# 9_7-13_3.net
KiCad netlist of a schematic drawn in Altium Designer
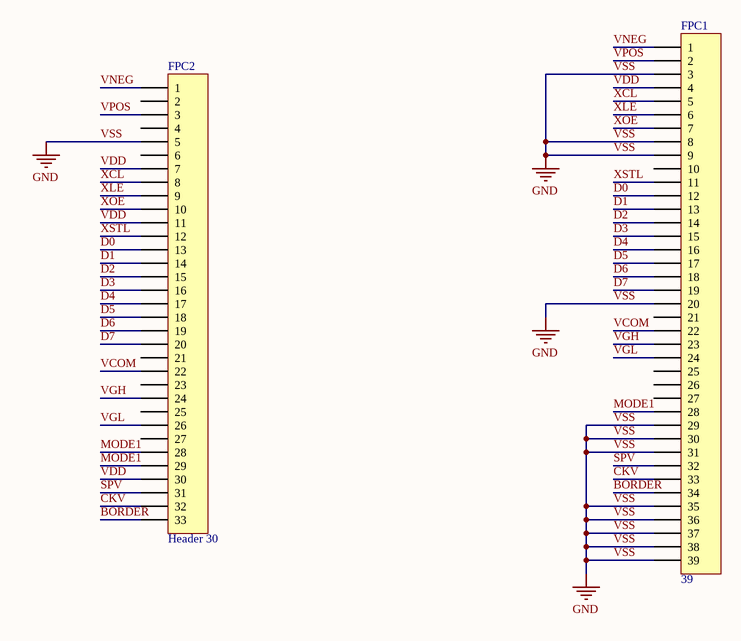
[diagram p0: 9.7-13.3.SchDoc]

(export (version "E")
  (design (tool "Eeschema 10.0.6"))
  (components
    (comp (ref "FPC1") (value "39") (footprint "1") (libsource (lib "9.7-13.3") (part "39")))
    (comp (ref "FPC2")
      (value "Header 30")
      (footprint "2")
      (description "Header, 30-Pin")
      (fields (field (name "PUBLISHER") "Altium Limited"))
      (libsource (lib "9.7-13.3") (part "Header 33"))
    )
  )
  (nets
    (net (code "2") (name "/BORDER") (class "Default")
      (node (ref "FPC1") (pin "34") (pinfunction "34_34") (pintype "passive"))
      (node (ref "FPC2") (pin "33") (pinfunction "33_33") (pintype "passive"))
    )
    (net (code "3") (name "/CKV") (class "Default")
      (node (ref "FPC1") (pin "33") (pinfunction "33_33") (pintype "passive"))
      (node (ref "FPC2") (pin "32") (pinfunction "32_32") (pintype "passive"))
    )
    (net (code "4") (name "/D0") (class "Default")
      (node (ref "FPC1") (pin "12") (pinfunction "12_12") (pintype "passive"))
      (node (ref "FPC2") (pin "13") (pinfunction "13_13") (pintype "passive"))
    )
    (net (code "5") (name "/D1") (class "Default")
      (node (ref "FPC1") (pin "13") (pinfunction "13_13") (pintype "passive"))
      (node (ref "FPC2") (pin "14") (pinfunction "14_14") (pintype "passive"))
    )
    (net (code "6") (name "/D2") (class "Default")
      (node (ref "FPC1") (pin "14") (pinfunction "14_14") (pintype "passive"))
      (node (ref "FPC2") (pin "15") (pinfunction "15_15") (pintype "passive"))
    )
    (net (code "7") (name "/D3") (class "Default")
      (node (ref "FPC1") (pin "15") (pinfunction "15_15") (pintype "passive"))
      (node (ref "FPC2") (pin "16") (pinfunction "16_16") (pintype "passive"))
    )
    (net (code "8") (name "/D4") (class "Default")
      (node (ref "FPC1") (pin "16") (pinfunction "16_16") (pintype "passive"))
      (node (ref "FPC2") (pin "17") (pinfunction "17_17") (pintype "passive"))
    )
    (net (code "9") (name "/D5") (class "Default")
      (node (ref "FPC1") (pin "17") (pinfunction "17_17") (pintype "passive"))
      (node (ref "FPC2") (pin "18") (pinfunction "18_18") (pintype "passive"))
    )
    (net (code "10") (name "/D6") (class "Default")
      (node (ref "FPC1") (pin "18") (pinfunction "18_18") (pintype "passive"))
      (node (ref "FPC2") (pin "19") (pinfunction "19_19") (pintype "passive"))
    )
    (net (code "11") (name "/D7") (class "Default")
      (node (ref "FPC1") (pin "19") (pinfunction "19_19") (pintype "passive"))
      (node (ref "FPC2") (pin "20") (pinfunction "20_20") (pintype "passive"))
    )
    (net (code "12") (name "/MODE1") (class "Default")
      (node (ref "FPC1") (pin "28") (pinfunction "28_28") (pintype "passive"))
      (node (ref "FPC2") (pin "28") (pinfunction "28_28") (pintype "passive"))
      (node (ref "FPC2") (pin "29") (pinfunction "29_29") (pintype "passive"))
    )
    (net (code "13") (name "/SPV") (class "Default")
      (node (ref "FPC1") (pin "32") (pinfunction "32_32") (pintype "passive"))
      (node (ref "FPC2") (pin "31") (pinfunction "31_31") (pintype "passive"))
    )
    (net (code "14") (name "/VCOM") (class "Default")
      (node (ref "FPC1") (pin "22") (pinfunction "22_22") (pintype "passive"))
      (node (ref "FPC2") (pin "22") (pinfunction "22_22") (pintype "passive"))
    )
    (net (code "15") (name "/VDD") (class "Default")
      (node (ref "FPC1") (pin "4") (pinfunction "4_4") (pintype "passive"))
      (node (ref "FPC2") (pin "11") (pinfunction "11_11") (pintype "passive"))
      (node (ref "FPC2") (pin "30") (pinfunction "30_30") (pintype "passive"))
      (node (ref "FPC2") (pin "7") (pinfunction "7_7") (pintype "passive"))
    )
    (net (code "16") (name "/VGH") (class "Default")
      (node (ref "FPC1") (pin "23") (pinfunction "23_23") (pintype "passive"))
      (node (ref "FPC2") (pin "24") (pinfunction "24_24") (pintype "passive"))
    )
    (net (code "17") (name "/VGL") (class "Default")
      (node (ref "FPC1") (pin "24") (pinfunction "24_24") (pintype "passive"))
      (node (ref "FPC2") (pin "26") (pinfunction "26_26") (pintype "passive"))
    )
    (net (code "18") (name "/VNEG") (class "Default")
      (node (ref "FPC1") (pin "1") (pinfunction "1_1") (pintype "passive"))
      (node (ref "FPC2") (pin "1") (pinfunction "1_1") (pintype "passive"))
    )
    (net (code "19") (name "/VPOS") (class "Default")
      (node (ref "FPC1") (pin "2") (pinfunction "2_2") (pintype "passive"))
      (node (ref "FPC2") (pin "3") (pinfunction "3_3") (pintype "passive"))
    )
    (net (code "20") (name "/XCL") (class "Default")
      (node (ref "FPC1") (pin "5") (pinfunction "5_5") (pintype "passive"))
      (node (ref "FPC2") (pin "8") (pinfunction "8_8") (pintype "passive"))
    )
    (net (code "21") (name "/XLE") (class "Default")
      (node (ref "FPC1") (pin "6") (pinfunction "6_6") (pintype "passive"))
      (node (ref "FPC2") (pin "9") (pinfunction "9_9") (pintype "passive"))
    )
    (net (code "22") (name "/XOE") (class "Default")
      (node (ref "FPC1") (pin "7") (pinfunction "7_7") (pintype "passive"))
      (node (ref "FPC2") (pin "10") (pinfunction "10_10") (pintype "passive"))
    )
    (net (code "23") (name "/XSTL") (class "Default")
      (node (ref "FPC1") (pin "11") (pinfunction "11_11") (pintype "passive"))
      (node (ref "FPC2") (pin "12") (pinfunction "12_12") (pintype "passive"))
    )
    (net (code "24") (name "GND") (class "Default")
      (node (ref "FPC1") (pin "20") (pinfunction "20_20") (pintype "passive"))
      (node (ref "FPC1") (pin "29") (pinfunction "29_29") (pintype "passive"))
      (node (ref "FPC1") (pin "3") (pinfunction "3_3") (pintype "passive"))
      (node (ref "FPC1") (pin "30") (pinfunction "30_30") (pintype "passive"))
      (node (ref "FPC1") (pin "31") (pinfunction "31_31") (pintype "passive"))
      (node (ref "FPC1") (pin "35") (pinfunction "35_35") (pintype "passive"))
      (node (ref "FPC1") (pin "36") (pinfunction "36_36") (pintype "passive"))
      (node (ref "FPC1") (pin "37") (pinfunction "37_37") (pintype "passive"))
      (node (ref "FPC1") (pin "38") (pinfunction "38_38") (pintype "passive"))
      (node (ref "FPC1") (pin "39") (pinfunction "39_39") (pintype "passive"))
      (node (ref "FPC1") (pin "8") (pinfunction "8_8") (pintype "passive"))
      (node (ref "FPC1") (pin "9") (pinfunction "9_9") (pintype "passive"))
      (node (ref "FPC2") (pin "5") (pinfunction "5_5") (pintype "passive"))
    )
    (net (code "25") (name "unconnected-(FPC1-Pad10)") (class "Default")
      (node (ref "FPC1") (pin "10") (pinfunction "10_10") (pintype "passive"))
    )
    (net (code "26") (name "unconnected-(FPC1-Pad21)") (class "Default")
      (node (ref "FPC1") (pin "21") (pinfunction "21_21") (pintype "passive"))
    )
    (net (code "27") (name "unconnected-(FPC1-Pad25)") (class "Default")
      (node (ref "FPC1") (pin "25") (pinfunction "25_25") (pintype "passive"))
    )
    (net (code "28") (name "unconnected-(FPC1-Pad26)") (class "Default")
      (node (ref "FPC1") (pin "26") (pinfunction "26_26") (pintype "passive"))
    )
    (net (code "29") (name "unconnected-(FPC1-Pad27)") (class "Default")
      (node (ref "FPC1") (pin "27") (pinfunction "27_27") (pintype "passive"))
    )
    (net (code "30") (name "unconnected-(FPC2-Pad2)") (class "Default")
      (node (ref "FPC2") (pin "2") (pinfunction "2_2") (pintype "passive"))
    )
    (net (code "31") (name "unconnected-(FPC2-Pad4)") (class "Default")
      (node (ref "FPC2") (pin "4") (pinfunction "4_4") (pintype "passive"))
    )
    (net (code "32") (name "unconnected-(FPC2-Pad6)") (class "Default")
      (node (ref "FPC2") (pin "6") (pinfunction "6_6") (pintype "passive"))
    )
    (net (code "33") (name "unconnected-(FPC2-Pad21)") (class "Default")
      (node (ref "FPC2") (pin "21") (pinfunction "21_21") (pintype "passive"))
    )
    (net (code "34") (name "unconnected-(FPC2-Pad23)") (class "Default")
      (node (ref "FPC2") (pin "23") (pinfunction "23_23") (pintype "passive"))
    )
    (net (code "35") (name "unconnected-(FPC2-Pad25)") (class "Default")
      (node (ref "FPC2") (pin "25") (pinfunction "25_25") (pintype "passive"))
    )
    (net (code "36") (name "unconnected-(FPC2-Pad27)") (class "Default")
      (node (ref "FPC2") (pin "27") (pinfunction "27_27") (pintype "passive"))
    )
  )
)
